# FPGA_JTAG.net
KiCad netlist of a schematic drawn in Altium Designer
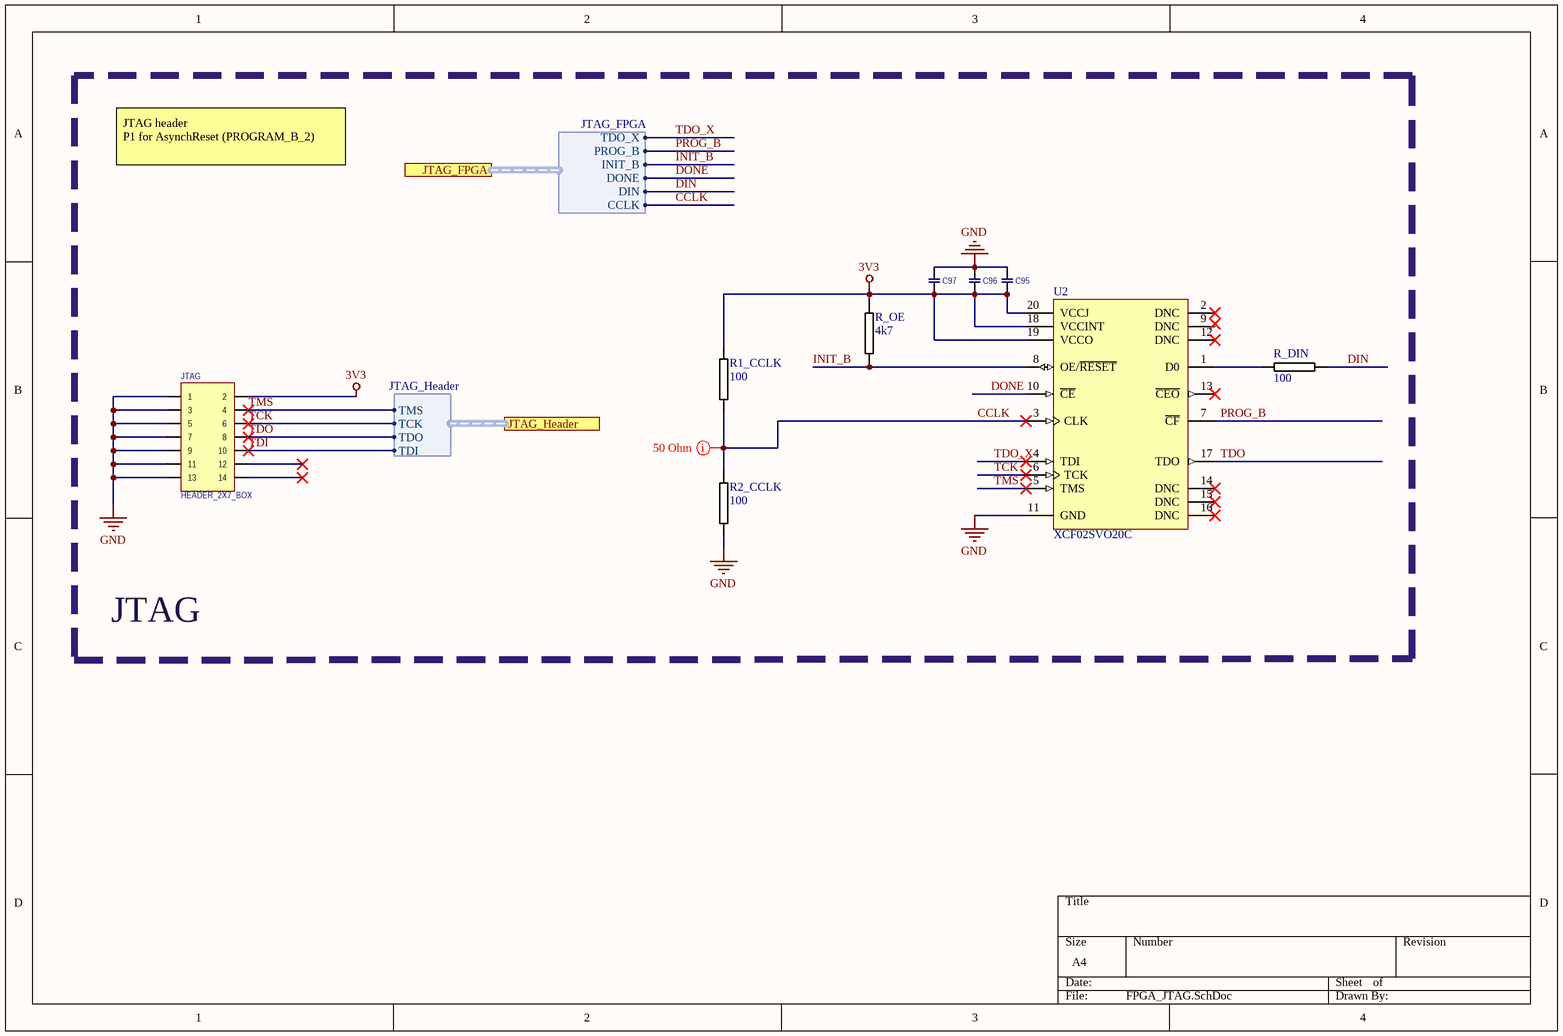
[diagram p0: FPGA_JTAG.SchDoc]

(export (version "E")
  (design (tool "Eeschema 10.0.6"))
  (components
    (comp (ref "C95")
      (value "100NF_0603_50V_X7R")
      (footprint "CAP0603")
      (description "128-8255    Capacitor MLC-X7R_0603_100NF_10%_50V; C0603C104K5RAC; KEMET; RoHS=Yes")
      (libsource (lib "ONEMULA_V2") (part "100NF_0603_50V_X7R"))
    )
    (comp (ref "C96")
      (value "470NF_0603_50V_X7R")
      (footprint "CAP0603")
      (description "128-8255    Capacitor MLC-X7R_0603_100NF_10%_50V; C0603C104K5RAC; KEMET; RoHS=Yes")
      (libsource (lib "ONEMULA_V2") (part "100NF_0603_50V_X7R"))
    )
    (comp (ref "C97")
      (value "1UF_0603_50V_X7R")
      (footprint "CAP0603")
      (description "128-8255    Capacitor MLC-X7R_0603_100NF_10%_50V; C0603C104K5RAC; KEMET; RoHS=Yes")
      (libsource (lib "ONEMULA_V2") (part "100NF_0603_50V_X7R"))
    )
    (comp (ref "JTAG")
      (value "HEADER_2X7_BOX")
      (footprint "X14ABPB")
      (libsource (lib "ONEMULA_V2") (part "HEADER_2X7_BOX"))
    )
    (comp (ref "R1_CCLK")
      (value "100")
      (footprint "0603R-TBD")
      (description "RESISTOR 0603 VALUE TO BE DETERMINED")
      (libsource (lib "vh_altium_library") (part "0603R-TBD"))
    )
    (comp (ref "R2_CCLK")
      (value "100")
      (footprint "0603R-TBD")
      (description "RESISTOR 0603 VALUE TO BE DETERMINED")
      (libsource (lib "vh_altium_library") (part "0603R-TBD"))
    )
    (comp (ref "R_DIN")
      (value "100")
      (footprint "0603R-TBD")
      (description "RESISTOR 0603 VALUE TO BE DETERMINED")
      (libsource (lib "vh_altium_library") (part "0603R-TBD"))
    )
    (comp (ref "R_OE")
      (value "4k7")
      (footprint "0603R-TBD")
      (description "RESISTOR 0603 VALUE TO BE DETERMINED")
      (libsource (lib "vh_altium_library") (part "0603R-TBD"))
    )
    (comp (ref "U2")
      (value "XCF02SVO20C")
      (footprint "VO20_N")
      (fields (field (name "PUBLISHER") "Altium Limited"))
      (libsource (lib "Xilinx XCF") (part "XCF02SVO20C"))
    )
  )
  (nets
    (net (code "3") (name "/CCLK") (class "Default")
      (node (ref "R1_CCLK") (pin "2") (pintype "passive"))
      (node (ref "R2_CCLK") (pin "1") (pintype "passive"))
      (node (ref "U2") (pin "3") (pinfunction "CLK_3") (pintype "input"))
    )
    (net (code "4") (name "/DIN") (class "Default") (node (ref "R_DIN") (pin "2") (pintype "passive")))
    (net (code "5") (name "/DONE") (class "Default")
      (node (ref "U2") (pin "10") (pinfunction "~{CE}_10") (pintype "input"))
    )
    (net (code "6") (name "/INIT_B") (class "Default")
      (node (ref "R_OE") (pin "2") (pintype "passive"))
      (node (ref "U2") (pin "8") (pinfunction "OE/~{RESET}_8") (pintype "bidirectional"))
    )
    (net (code "7") (name "/PROG_B") (class "Default")
      (node (ref "U2") (pin "7") (pinfunction "~{CF}_7") (pintype "open_collector"))
    )
    (net (code "8") (name "/TCK") (class "Default")
      (node (ref "JTAG") (pin "6") (pinfunction "6_6") (pintype "passive"))
      (node (ref "U2") (pin "6") (pinfunction "TCK_6") (pintype "input"))
    )
    (net (code "9") (name "/TDI") (class "Default")
      (node (ref "JTAG") (pin "10") (pinfunction "10_10") (pintype "passive+no_connect"))
    )
    (net (code "10") (name "/TDO") (class "Default")
      (node (ref "JTAG") (pin "8") (pinfunction "8_8") (pintype "passive"))
      (node (ref "U2") (pin "17") (pinfunction "TDO_17") (pintype "output"))
    )
    (net (code "11") (name "/TDO_X") (class "Default")
      (node (ref "U2") (pin "4") (pinfunction "TDI_4") (pintype "input+no_connect"))
    )
    (net (code "12") (name "/TMS") (class "Default")
      (node (ref "JTAG") (pin "4") (pinfunction "4_4") (pintype "passive"))
      (node (ref "U2") (pin "5") (pinfunction "TMS_5") (pintype "input"))
    )
    (net (code "15") (name "3V3") (class "Default")
      (node (ref "C95") (pin "2") (pinfunction "2_2") (pintype "passive"))
      (node (ref "C96") (pin "2") (pinfunction "2_2") (pintype "passive"))
      (node (ref "C97") (pin "2") (pinfunction "2_2") (pintype "passive"))
      (node (ref "JTAG") (pin "2") (pinfunction "2_2") (pintype "passive"))
      (node (ref "R1_CCLK") (pin "1") (pintype "passive"))
      (node (ref "R_OE") (pin "1") (pintype "passive"))
      (node (ref "U2") (pin "18") (pinfunction "VCCINT_18") (pintype "power_in"))
      (node (ref "U2") (pin "19") (pinfunction "VCCO_19") (pintype "power_in"))
      (node (ref "U2") (pin "20") (pinfunction "VCCJ_20") (pintype "power_in"))
    )
    (net (code "16") (name "GND") (class "Default")
      (node (ref "C95") (pin "1") (pinfunction "1_1") (pintype "passive"))
      (node (ref "C96") (pin "1") (pinfunction "1_1") (pintype "passive"))
      (node (ref "C97") (pin "1") (pinfunction "1_1") (pintype "passive"))
      (node (ref "JTAG") (pin "1") (pinfunction "1_1") (pintype "passive"))
      (node (ref "JTAG") (pin "11") (pinfunction "11_11") (pintype "passive"))
      (node (ref "JTAG") (pin "13") (pinfunction "13_13") (pintype "passive"))
      (node (ref "JTAG") (pin "3") (pinfunction "3_3") (pintype "passive"))
      (node (ref "JTAG") (pin "5") (pinfunction "5_5") (pintype "passive"))
      (node (ref "JTAG") (pin "7") (pinfunction "7_7") (pintype "passive"))
      (node (ref "JTAG") (pin "9") (pinfunction "9_9") (pintype "passive"))
      (node (ref "R2_CCLK") (pin "2") (pintype "passive"))
      (node (ref "U2") (pin "11") (pinfunction "GND_11") (pintype "power_in"))
    )
    (net (code "17") (name "Net-(U2-D0)") (class "Default")
      (node (ref "R_DIN") (pin "1") (pintype "passive"))
      (node (ref "U2") (pin "1") (pinfunction "D0_1") (pintype "tri_state"))
    )
    (net (code "18") (name "unconnected-(JTAG-Pad12)") (class "Default")
      (node (ref "JTAG") (pin "12") (pinfunction "12_12") (pintype "passive+no_connect"))
    )
    (net (code "19") (name "unconnected-(JTAG-Pad14)") (class "Default")
      (node (ref "JTAG") (pin "14") (pinfunction "14_14") (pintype "passive+no_connect"))
    )
    (net (code "20") (name "unconnected-(U2-DNC-Pad2)") (class "Default")
      (node (ref "U2") (pin "2") (pinfunction "DNC_2") (pintype "passive+no_connect"))
    )
    (net (code "21") (name "unconnected-(U2-DNC-Pad9)") (class "Default")
      (node (ref "U2") (pin "9") (pinfunction "DNC_9") (pintype "passive"))
    )
    (net (code "22") (name "unconnected-(U2-DNC-Pad12)") (class "Default")
      (node (ref "U2") (pin "12") (pinfunction "DNC_12") (pintype "passive+no_connect"))
    )
    (net (code "23") (name "unconnected-(U2-DNC-Pad14)") (class "Default")
      (node (ref "U2") (pin "14") (pinfunction "DNC_14") (pintype "passive+no_connect"))
    )
    (net (code "24") (name "unconnected-(U2-DNC-Pad15)") (class "Default")
      (node (ref "U2") (pin "15") (pinfunction "DNC_15") (pintype "passive+no_connect"))
    )
    (net (code "25") (name "unconnected-(U2-DNC-Pad16)") (class "Default")
      (node (ref "U2") (pin "16") (pinfunction "DNC_16") (pintype "passive+no_connect"))
    )
    (net (code "26") (name "unconnected-(U2-~{CEO}-Pad13)") (class "Default")
      (node (ref "U2") (pin "13") (pinfunction "~{CEO}_13") (pintype "output+no_connect"))
    )
  )
)
